# Adafruit_TSL2591.net
KiCad netlist of a schematic drawn in EAGLE
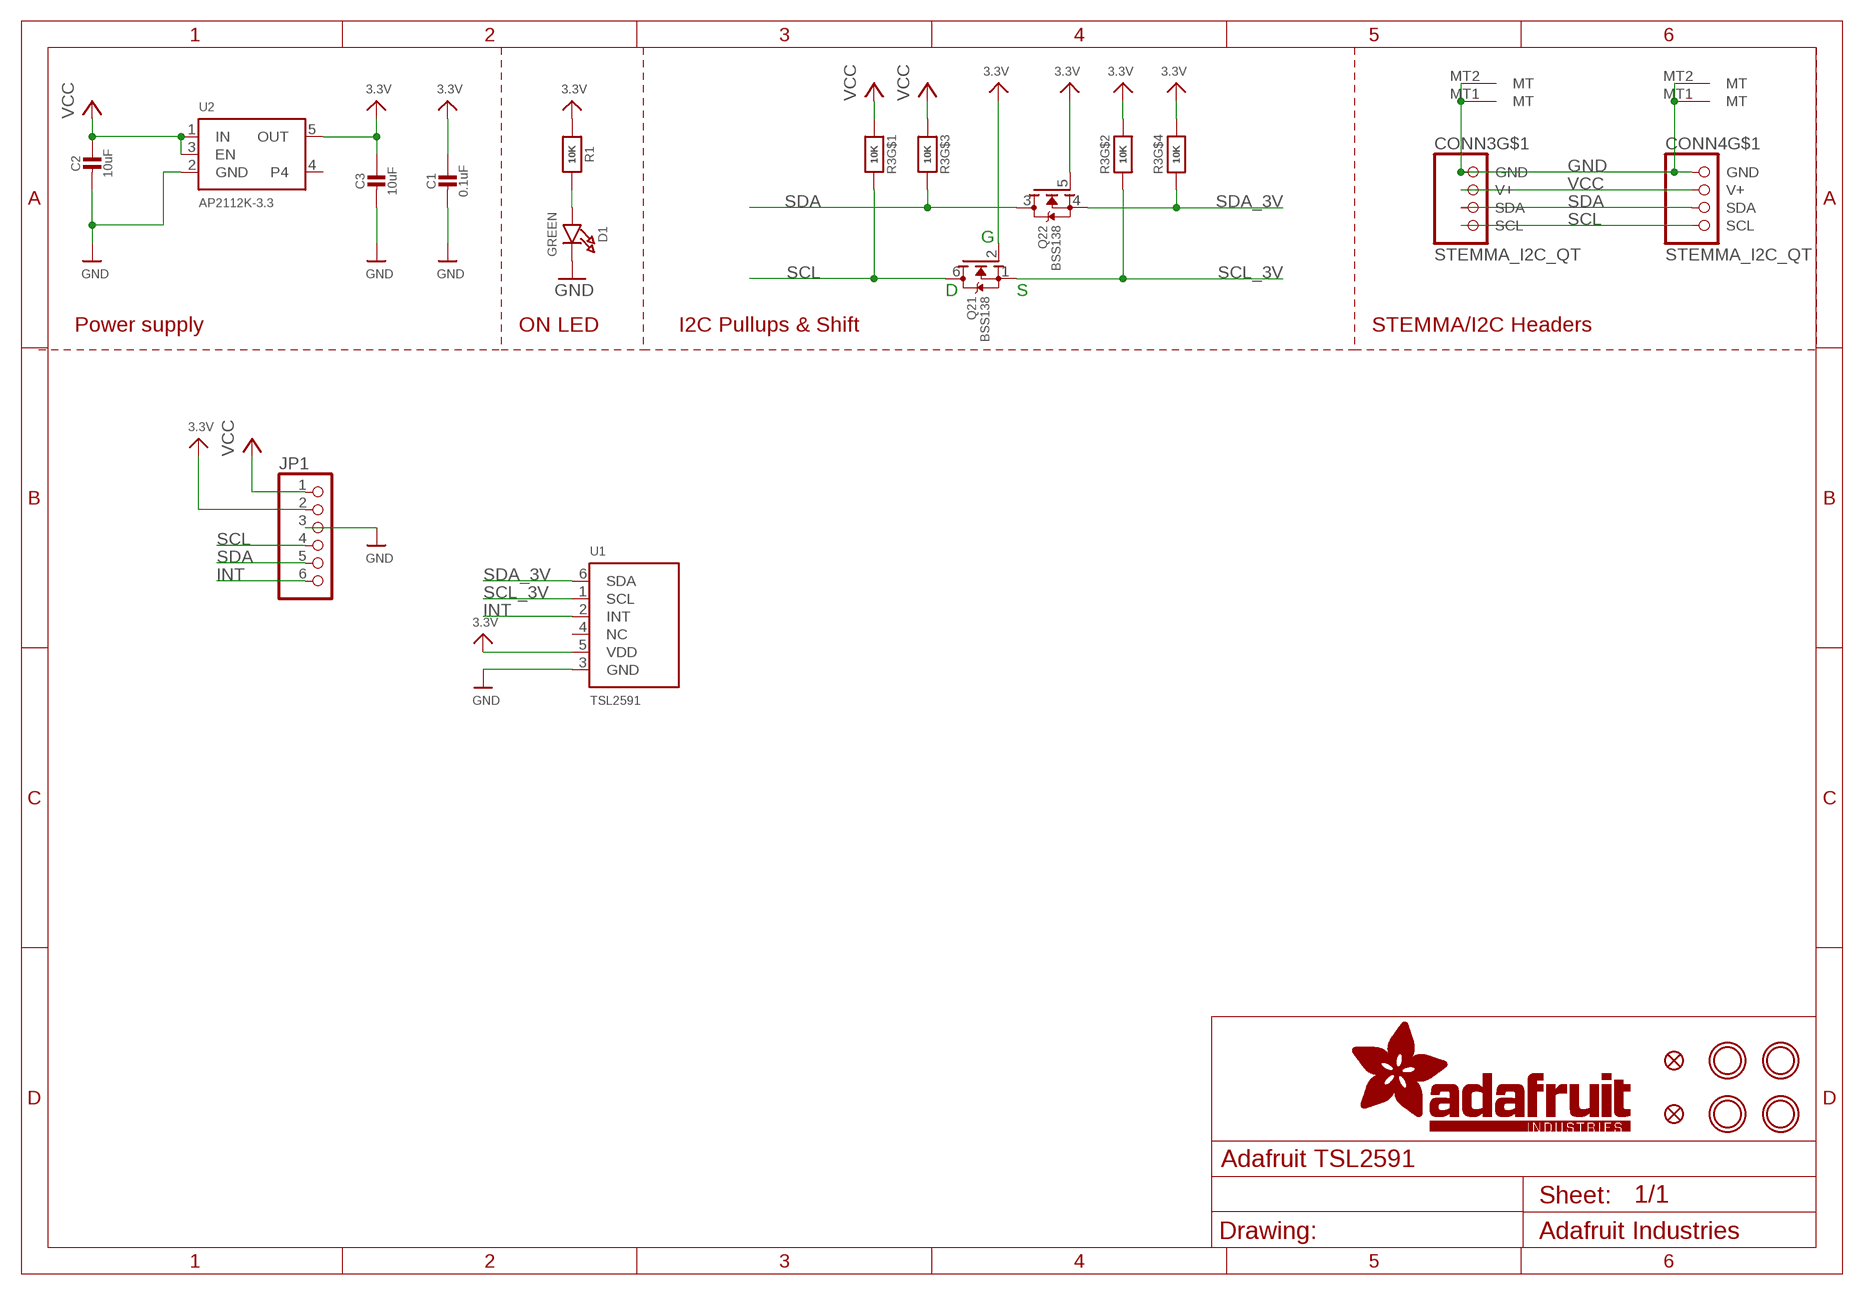
[diagram p0: schematic, sheet 1]

(export (version "E")
  (design (tool "Eeschema 10.0.6"))
  (components
    (comp (ref "C1")
      (value "0.1uF")
      (footprint "eagle-import:0603-NO")
      (libsource (lib "eagle-import") (part "CAP_CERAMIC0603_NO"))
    )
    (comp (ref "C2")
      (value "10uF")
      (footprint "eagle-import:0805-NO")
      (libsource (lib "eagle-import") (part "CAP_CERAMIC0805-NOOUTLINE"))
    )
    (comp (ref "C3")
      (value "10uF")
      (footprint "eagle-import:0805-NO")
      (libsource (lib "eagle-import") (part "CAP_CERAMIC0805-NOOUTLINE"))
    )
    (comp (ref "CONN3")
      (value "STEMMA_I2C_QT")
      (footprint "eagle-import:JST_SH4")
      (libsource (lib "eagle-import") (part "STEMMA_I2C_QT"))
    )
    (comp (ref "CONN4")
      (value "STEMMA_I2C_QT")
      (footprint "eagle-import:JST_SH4")
      (libsource (lib "eagle-import") (part "STEMMA_I2C_QT"))
    )
    (comp (ref "D1")
      (value "GREEN")
      (footprint "eagle-import:CHIPLED_0603_NOOUTLINE")
      (libsource (lib "eagle-import") (part "LED0603_NOOUTLINE"))
    )
    (comp (ref "FID3")
      (value "FIDUCIAL_1MM")
      (footprint "eagle-import:FIDUCIAL_1MM")
      (libsource (lib "eagle-import") (part "FIDUCIAL_1MM"))
    )
    (comp (ref "FID4")
      (value "FIDUCIAL_1MM")
      (footprint "eagle-import:FIDUCIAL_1MM")
      (libsource (lib "eagle-import") (part "FIDUCIAL_1MM"))
    )
    (comp (ref "JP1")
      (value "HEADER-1X670MIL")
      (footprint "eagle-import:1X06_ROUND_70")
      (libsource (lib "eagle-import") (part "HEADER-1X670MIL"))
    )
    (comp (ref "Q2")
      (value "BSS138")
      (footprint "eagle-import:SOT363")
      (libsource (lib "eagle-import") (part "MOSFET-N_DUAL"))
    )
    (comp (ref "R1")
      (value "10K")
      (footprint "eagle-import:0603-NO")
      (libsource (lib "eagle-import") (part "RESISTOR_0603_NOOUT"))
    )
    (comp (ref "R3")
      (value "10K")
      (footprint "eagle-import:RESPACK_4X0603")
      (libsource (lib "eagle-import") (part "RESISTOR_4PACK"))
    )
    (comp (ref "U$1")
      (value "MOUNTINGHOLE2.5")
      (footprint "eagle-import:MOUNTINGHOLE_2.5_PLATED")
      (libsource (lib "eagle-import") (part "MOUNTINGHOLE2.5"))
    )
    (comp (ref "U$17")
      (value "MOUNTINGHOLE2.5")
      (footprint "eagle-import:MOUNTINGHOLE_2.5_PLATED")
      (libsource (lib "eagle-import") (part "MOUNTINGHOLE2.5"))
    )
    (comp (ref "U$19")
      (value "MOUNTINGHOLE2.5")
      (footprint "eagle-import:MOUNTINGHOLE_2.5_PLATED")
      (libsource (lib "eagle-import") (part "MOUNTINGHOLE2.5"))
    )
    (comp (ref "U$21")
      (value "MOUNTINGHOLE2.5")
      (footprint "eagle-import:MOUNTINGHOLE_2.5_PLATED")
      (libsource (lib "eagle-import") (part "MOUNTINGHOLE2.5"))
    )
    (comp (ref "U1")
      (value "TSL2591")
      (footprint "eagle-import:DFN6_TAOS")
      (libsource (lib "eagle-import") (part "LIGHT_TSL2591"))
    )
    (comp (ref "U2")
      (value "AP2112K-3.3")
      (footprint "eagle-import:SOT23-5")
      (libsource (lib "eagle-import") (part "VREG_SOT23-5"))
    )
  )
  (nets
    (net (code "1") (name "/INT") (class "Default")
      (node (ref "JP1") (pin "6") (pinfunction "6_6") (pintype "passive"))
      (node (ref "U1") (pin "2") (pinfunction "INT_2") (pintype "output"))
    )
    (net (code "2") (name "/SCL") (class "Default")
      (node (ref "CONN3") (pin "4") (pinfunction "SCL_4") (pintype "passive"))
      (node (ref "CONN4") (pin "4") (pinfunction "SCL_4") (pintype "passive"))
      (node (ref "JP1") (pin "4") (pinfunction "4_4") (pintype "passive"))
      (node (ref "Q2") (pin "6") (pinfunction "D_6") (pintype "bidirectional"))
      (node (ref "R3") (pin "8") (pinfunction "2_8") (pintype "passive"))
    )
    (net (code "3") (name "/SCL_3V") (class "Default")
      (node (ref "Q2") (pin "1") (pinfunction "S_1") (pintype "bidirectional"))
      (node (ref "R3") (pin "7") (pinfunction "2_7") (pintype "passive"))
      (node (ref "U1") (pin "1") (pinfunction "SCL_1") (pintype "bidirectional"))
    )
    (net (code "4") (name "/SDA") (class "Default")
      (node (ref "CONN3") (pin "3") (pinfunction "SDA_3") (pintype "passive"))
      (node (ref "CONN4") (pin "3") (pinfunction "SDA_3") (pintype "passive"))
      (node (ref "JP1") (pin "5") (pinfunction "5_5") (pintype "passive"))
      (node (ref "Q2") (pin "3") (pinfunction "D_3") (pintype "bidirectional"))
      (node (ref "R3") (pin "6") (pinfunction "2_6") (pintype "passive"))
    )
    (net (code "5") (name "/SDA_3V") (class "Default")
      (node (ref "Q2") (pin "4") (pinfunction "S_4") (pintype "bidirectional"))
      (node (ref "R3") (pin "5") (pinfunction "2_5") (pintype "passive"))
      (node (ref "U1") (pin "6") (pinfunction "SDA_6") (pintype "bidirectional"))
    )
    (net (code "6") (name "3.3V") (class "Default")
      (node (ref "C1") (pin "1") (pinfunction "1_1") (pintype "passive"))
      (node (ref "C3") (pin "1") (pinfunction "1_1") (pintype "passive"))
      (node (ref "JP1") (pin "2") (pinfunction "2_2") (pintype "passive"))
      (node (ref "Q2") (pin "2") (pinfunction "G_2") (pintype "bidirectional"))
      (node (ref "Q2") (pin "5") (pinfunction "G_5") (pintype "bidirectional"))
      (node (ref "R1") (pin "1") (pinfunction "1_1") (pintype "passive"))
      (node (ref "R3") (pin "2") (pinfunction "1_2") (pintype "passive"))
      (node (ref "R3") (pin "4") (pinfunction "1_4") (pintype "passive"))
      (node (ref "U1") (pin "5") (pinfunction "VDD_5") (pintype "power_in"))
      (node (ref "U2") (pin "5") (pinfunction "OUT_5") (pintype "power_in"))
    )
    (net (code "7") (name "GND") (class "Default")
      (node (ref "C1") (pin "2") (pinfunction "2_2") (pintype "passive"))
      (node (ref "C2") (pin "2") (pinfunction "2_2") (pintype "passive"))
      (node (ref "C3") (pin "2") (pinfunction "2_2") (pintype "passive"))
      (node (ref "CONN3") (pin "1") (pinfunction "GND_1") (pintype "passive"))
      (node (ref "CONN3") (pin "MT1") (pinfunction "MT_MT1") (pintype "bidirectional"))
      (node (ref "CONN3") (pin "MT2") (pinfunction "MT_MT2") (pintype "bidirectional"))
      (node (ref "CONN4") (pin "1") (pinfunction "GND_1") (pintype "passive"))
      (node (ref "CONN4") (pin "MT1") (pinfunction "MT_MT1") (pintype "bidirectional"))
      (node (ref "CONN4") (pin "MT2") (pinfunction "MT_MT2") (pintype "bidirectional"))
      (node (ref "D1") (pin "C") (pinfunction "C_C") (pintype "passive"))
      (node (ref "JP1") (pin "3") (pinfunction "3_3") (pintype "passive"))
      (node (ref "U1") (pin "3") (pinfunction "GND_3") (pintype "power_in"))
      (node (ref "U2") (pin "2") (pinfunction "GND_2") (pintype "power_in"))
    )
    (net (code "8") (name "Net-(D1-PadA)") (class "Default")
      (node (ref "D1") (pin "A") (pinfunction "A_A") (pintype "passive"))
      (node (ref "R1") (pin "2") (pinfunction "2_2") (pintype "passive"))
    )
    (net (code "9") (name "VCC") (class "Default")
      (node (ref "C2") (pin "1") (pinfunction "1_1") (pintype "passive"))
      (node (ref "CONN3") (pin "2") (pinfunction "V+_2") (pintype "passive"))
      (node (ref "CONN4") (pin "2") (pinfunction "V+_2") (pintype "passive"))
      (node (ref "JP1") (pin "1") (pinfunction "1_1") (pintype "passive"))
      (node (ref "R3") (pin "1") (pinfunction "1_1") (pintype "passive"))
      (node (ref "R3") (pin "3") (pinfunction "1_3") (pintype "passive"))
      (node (ref "U2") (pin "1") (pinfunction "IN_1") (pintype "power_in"))
      (node (ref "U2") (pin "3") (pinfunction "EN_3") (pintype "input"))
    )
    (net (code "10") (name "unconnected-(U1-NC-Pad4)") (class "Default")
      (node (ref "U1") (pin "4") (pinfunction "NC_4") (pintype "no_connect"))
    )
    (net (code "11") (name "unconnected-(U2-P4-Pad4)") (class "Default")
      (node (ref "U2") (pin "4") (pinfunction "P4_4") (pintype "bidirectional"))
    )
  )
)
